# univ_3-2-1-x-rev2.net
KiCad netlist of a schematic drawn in EAGLE
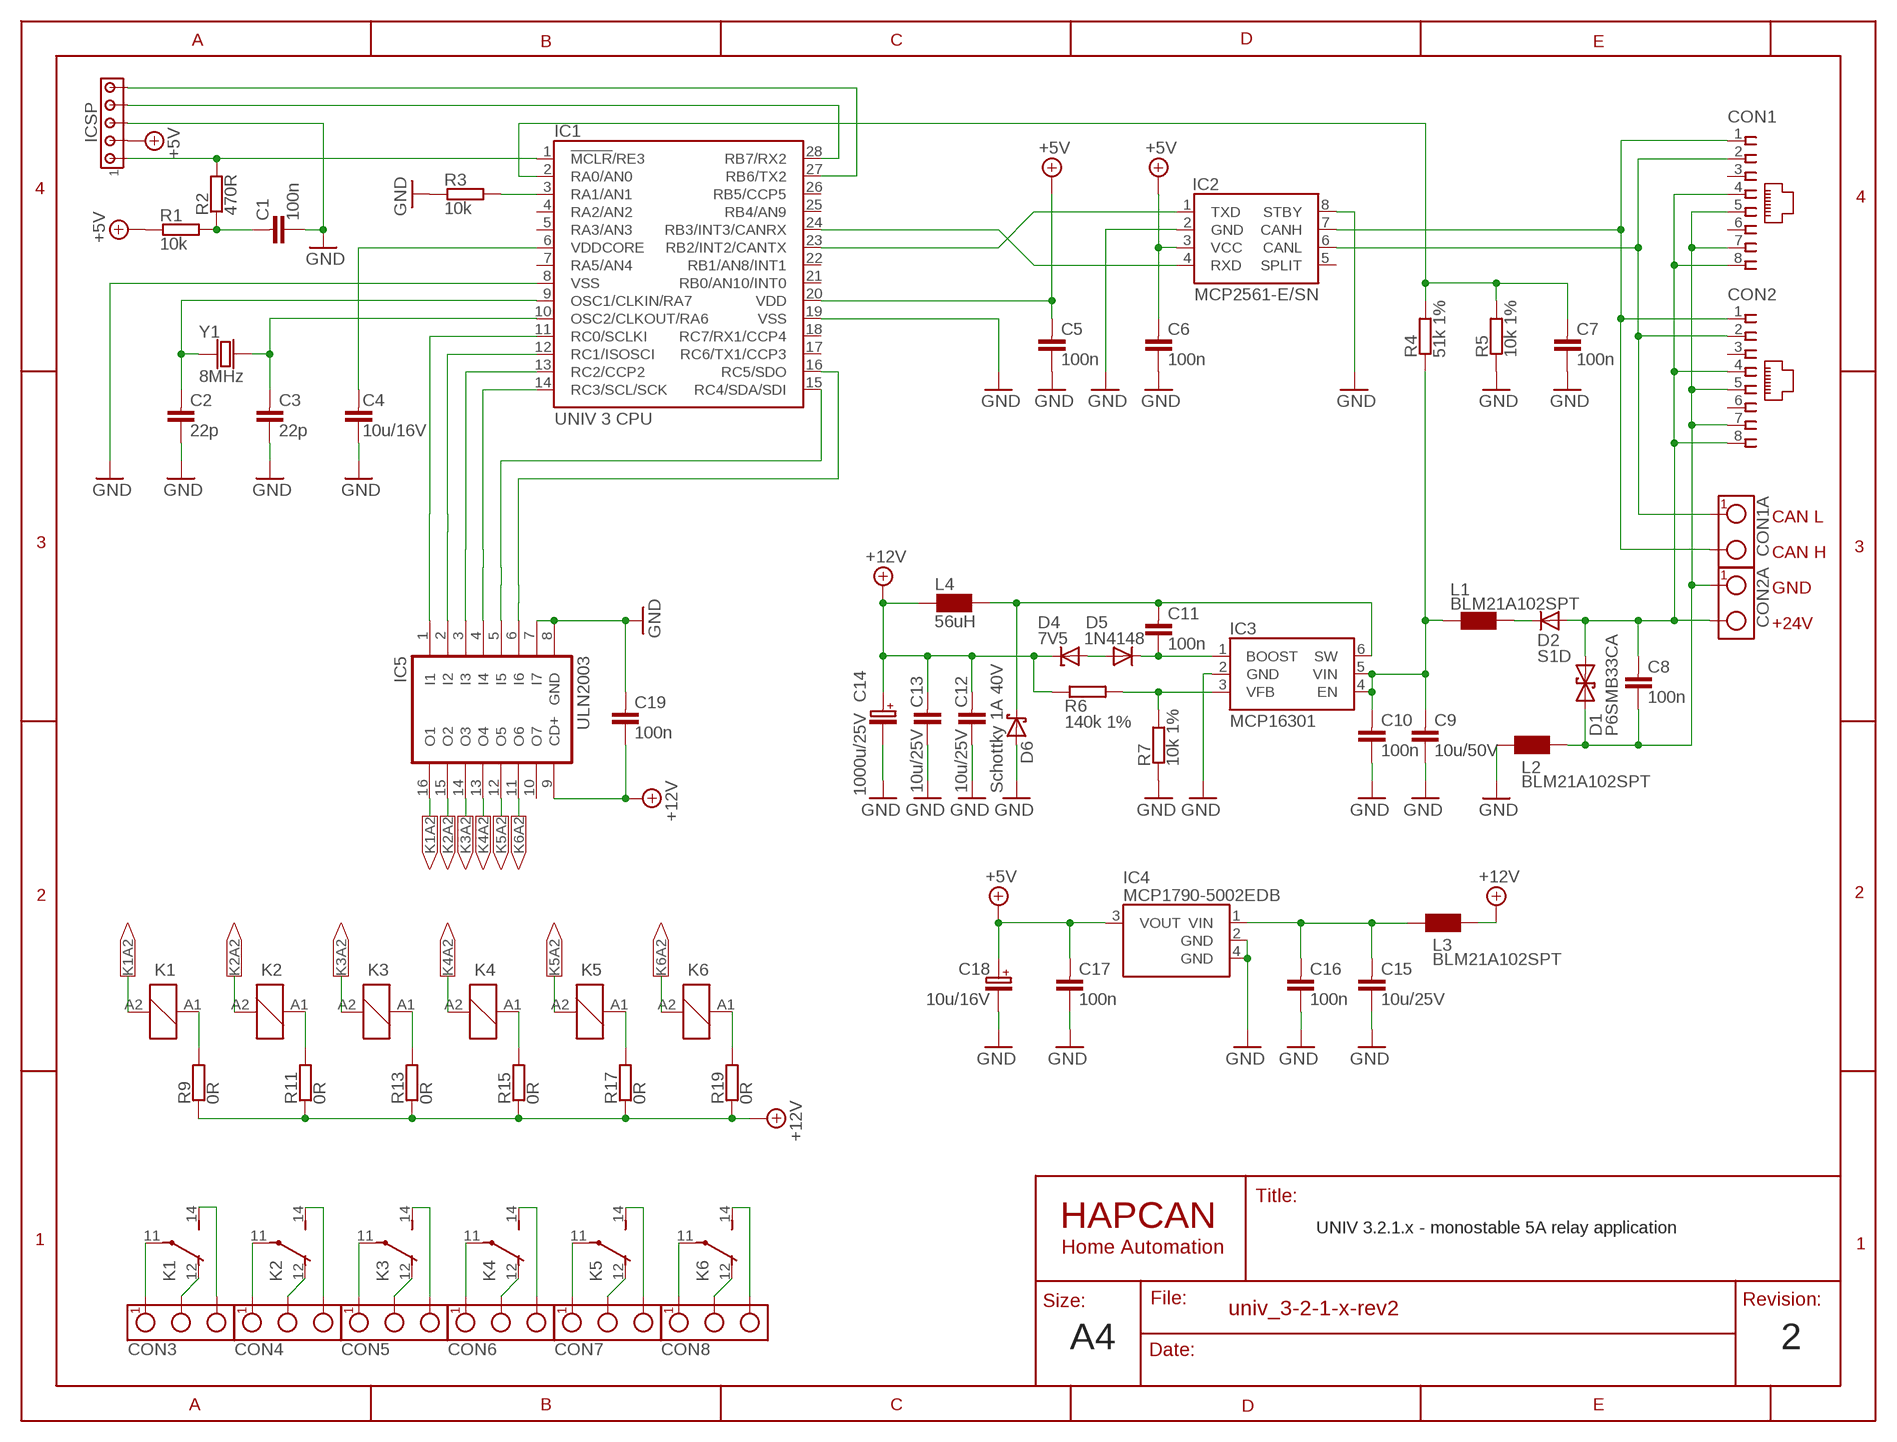
[diagram p0: schematic, sheet 1]

(export (version "E")
  (design (tool "Eeschema 10.0.6"))
  (components
    (comp (ref "C1")
      (value "100n")
      (footprint "eagle-import:0805")
      (libsource (lib "eagle-import") (part "CAPACITOR0805"))
    )
    (comp (ref "C2")
      (value "22p")
      (footprint "eagle-import:0805")
      (libsource (lib "eagle-import") (part "CAPACITOR0805"))
    )
    (comp (ref "C3")
      (value "22p")
      (footprint "eagle-import:0805")
      (libsource (lib "eagle-import") (part "CAPACITOR0805"))
    )
    (comp (ref "C4")
      (value "10u/16V")
      (footprint "eagle-import:0805")
      (libsource (lib "eagle-import") (part "CAPACITOR0805"))
    )
    (comp (ref "C5")
      (value "100n")
      (footprint "eagle-import:0805")
      (libsource (lib "eagle-import") (part "CAPACITOR0805"))
    )
    (comp (ref "C6")
      (value "100n")
      (footprint "eagle-import:0805")
      (libsource (lib "eagle-import") (part "CAPACITOR0805"))
    )
    (comp (ref "C7")
      (value "100n")
      (footprint "eagle-import:0805")
      (libsource (lib "eagle-import") (part "CAPACITOR0805"))
    )
    (comp (ref "C8")
      (value "100n")
      (footprint "eagle-import:0805")
      (libsource (lib "eagle-import") (part "CAPACITOR0805"))
    )
    (comp (ref "C9")
      (value "10u/50V")
      (footprint "eagle-import:1210")
      (libsource (lib "eagle-import") (part "CAPACITOR1210"))
    )
    (comp (ref "C10")
      (value "100n")
      (footprint "eagle-import:0805")
      (libsource (lib "eagle-import") (part "CAPACITOR0805"))
    )
    (comp (ref "C11")
      (value "100n")
      (footprint "eagle-import:0805")
      (libsource (lib "eagle-import") (part "CAPACITOR0805"))
    )
    (comp (ref "C12")
      (value "10u/25V")
      (footprint "eagle-import:1206")
      (libsource (lib "eagle-import") (part "CAPACITOR1206"))
    )
    (comp (ref "C13")
      (value "10u/25V")
      (footprint "eagle-import:1206")
      (libsource (lib "eagle-import") (part "CAPACITOR1206"))
    )
    (comp (ref "C14")
      (value "1000u/25V")
      (footprint "eagle-import:CAP-5X10.5")
      (libsource (lib "eagle-import") (part "CAPACITOR-POLARIZED-5X10.5"))
    )
    (comp (ref "C15")
      (value "10u/25V")
      (footprint "eagle-import:1206")
      (libsource (lib "eagle-import") (part "CAPACITOR1206"))
    )
    (comp (ref "C16")
      (value "100n")
      (footprint "eagle-import:0805")
      (libsource (lib "eagle-import") (part "CAPACITOR0805"))
    )
    (comp (ref "C17")
      (value "100n")
      (footprint "eagle-import:0805")
      (libsource (lib "eagle-import") (part "CAPACITOR0805"))
    )
    (comp (ref "C18")
      (value "10u/16V")
      (footprint "eagle-import:SMC_B")
      (libsource (lib "eagle-import") (part "CAPACITOR-POLARIZED-SMC_B"))
    )
    (comp (ref "C19")
      (value "100n")
      (footprint "eagle-import:0805")
      (libsource (lib "eagle-import") (part "CAPACITOR0805"))
    )
    (comp (ref "CON1")
      (value "RJ45-SOCKET")
      (footprint "eagle-import:RJ45-PCB-SOCKET")
      (libsource (lib "eagle-import") (part "RJ45-SOCKET"))
    )
    (comp (ref "CON1A")
      (value "TERMINAL-2")
      (footprint "eagle-import:ARK2-5X10,5MM")
      (libsource (lib "eagle-import") (part "TERMINAL-2-5X10,5MM"))
    )
    (comp (ref "CON2")
      (value "RJ45-SOCKET")
      (footprint "eagle-import:RJ45-PCB-SOCKET")
      (libsource (lib "eagle-import") (part "RJ45-SOCKET"))
    )
    (comp (ref "CON2A")
      (value "TERMINAL-2")
      (footprint "eagle-import:ARK2-5X10,5MM")
      (libsource (lib "eagle-import") (part "TERMINAL-2-5X10,5MM"))
    )
    (comp (ref "CON3")
      (value "TERMINAL-3-5X10.5MM")
      (footprint "eagle-import:ARK3-5X10.5MM")
      (libsource (lib "eagle-import") (part "TERMINAL-3-5X10.5MM"))
    )
    (comp (ref "CON4")
      (value "TERMINAL-3-5X10.5MM")
      (footprint "eagle-import:ARK3-5X10.5MM")
      (libsource (lib "eagle-import") (part "TERMINAL-3-5X10.5MM"))
    )
    (comp (ref "CON5")
      (value "TERMINAL-3-5X10.5MM")
      (footprint "eagle-import:ARK3-5X10.5MM")
      (libsource (lib "eagle-import") (part "TERMINAL-3-5X10.5MM"))
    )
    (comp (ref "CON6")
      (value "TERMINAL-3-5X10.5MM")
      (footprint "eagle-import:ARK3-5X10.5MM")
      (libsource (lib "eagle-import") (part "TERMINAL-3-5X10.5MM"))
    )
    (comp (ref "CON7")
      (value "TERMINAL-3-5X10.5MM")
      (footprint "eagle-import:ARK3-5X10.5MM")
      (libsource (lib "eagle-import") (part "TERMINAL-3-5X10.5MM"))
    )
    (comp (ref "CON8")
      (value "TERMINAL-3-5X10.5MM")
      (footprint "eagle-import:ARK3-5X10.5MM")
      (libsource (lib "eagle-import") (part "TERMINAL-3-5X10.5MM"))
    )
    (comp (ref "D1")
      (value "P6SMB33CA")
      (footprint "eagle-import:DO-214_TRANSIL2")
      (libsource (lib "eagle-import") (part "DIODE_TRANSIL2"))
    )
    (comp (ref "D2")
      (value "S1D")
      (footprint "eagle-import:DO-214")
      (libsource (lib "eagle-import") (part "DIODE_DO-214"))
    )
    (comp (ref "D4")
      (value "7V5")
      (footprint "eagle-import:SOD-80")
      (libsource (lib "eagle-import") (part "DIODE_ZENER_SOD-80"))
    )
    (comp (ref "D5")
      (value "1N4148")
      (footprint "eagle-import:0805")
      (libsource (lib "eagle-import") (part "DIODE_0805"))
    )
    (comp (ref "D6")
      (value "Schottky 1A 40V")
      (footprint "eagle-import:DO-214")
      (libsource (lib "eagle-import") (part "DIODE_TRANSIL1_DO214"))
    )
    (comp (ref "IC1")
      (value "UNIV 3 CPU")
      (footprint "eagle-import:UNIV3CPU")
      (libsource (lib "eagle-import") (part "UNIV3CPU-I/SO"))
    )
    (comp (ref "IC2")
      (value "MCP2561-E/SN")
      (footprint "eagle-import:SO-08")
      (libsource (lib "eagle-import") (part "MCP2561-E/SN"))
    )
    (comp (ref "IC3")
      (value "MCP16301")
      (footprint "eagle-import:SOT-23-6")
      (libsource (lib "eagle-import") (part "MCP16301SOT23-6"))
    )
    (comp (ref "IC4")
      (value "MCP1790-5002EDB")
      (footprint "eagle-import:SOT-223")
      (libsource (lib "eagle-import") (part "MCP1826SOT223-3"))
    )
    (comp (ref "IC5")
      (value "ULN2003")
      (footprint "eagle-import:SO-16")
      (libsource (lib "eagle-import") (part "ULN2003"))
    )
    (comp (ref "ICSP")
      (value "HEADER5")
      (footprint "eagle-import:SIP-5")
      (libsource (lib "eagle-import") (part "HEADER5"))
    )
    (comp (ref "K1")
      (value "RELAY_PE")
      (footprint "eagle-import:RELAY_PE")
      (libsource (lib "eagle-import") (part "RELAY_PE"))
    )
    (comp (ref "K2")
      (value "RELAY_PE")
      (footprint "eagle-import:RELAY_PE")
      (libsource (lib "eagle-import") (part "RELAY_PE"))
    )
    (comp (ref "K3")
      (value "RELAY_PE")
      (footprint "eagle-import:RELAY_PE")
      (libsource (lib "eagle-import") (part "RELAY_PE"))
    )
    (comp (ref "K4")
      (value "RELAY_PE")
      (footprint "eagle-import:RELAY_PE")
      (libsource (lib "eagle-import") (part "RELAY_PE"))
    )
    (comp (ref "K5")
      (value "RELAY_PE")
      (footprint "eagle-import:RELAY_PE")
      (libsource (lib "eagle-import") (part "RELAY_PE"))
    )
    (comp (ref "K6")
      (value "RELAY_PE")
      (footprint "eagle-import:RELAY_PE")
      (libsource (lib "eagle-import") (part "RELAY_PE"))
    )
    (comp (ref "L1")
      (value "BLM21A102SPT")
      (footprint "eagle-import:0805")
      (libsource (lib "eagle-import") (part "CHOKE0805"))
    )
    (comp (ref "L2")
      (value "BLM21A102SPT")
      (footprint "eagle-import:0805")
      (libsource (lib "eagle-import") (part "CHOKE0805"))
    )
    (comp (ref "L3")
      (value "BLM21A102SPT")
      (footprint "eagle-import:0805")
      (libsource (lib "eagle-import") (part "CHOKE0805"))
    )
    (comp (ref "L4")
      (value "56uH")
      (footprint "eagle-import:CHOKE-DER0705")
      (libsource (lib "eagle-import") (part "CHOKEDER0705"))
    )
    (comp (ref "R1")
      (value "10k")
      (footprint "eagle-import:0805")
      (libsource (lib "eagle-import") (part "RESISTOR0805"))
    )
    (comp (ref "R2")
      (value "470R")
      (footprint "eagle-import:0805")
      (libsource (lib "eagle-import") (part "RESISTOR0805"))
    )
    (comp (ref "R3")
      (value "10k")
      (footprint "eagle-import:0805")
      (libsource (lib "eagle-import") (part "RESISTOR0805"))
    )
    (comp (ref "R4")
      (value "51k 1%")
      (footprint "eagle-import:0805")
      (libsource (lib "eagle-import") (part "RESISTOR0805"))
    )
    (comp (ref "R5")
      (value "10k 1%")
      (footprint "eagle-import:0805")
      (libsource (lib "eagle-import") (part "RESISTOR0805"))
    )
    (comp (ref "R6")
      (value "140k 1%")
      (footprint "eagle-import:0805")
      (libsource (lib "eagle-import") (part "RESISTOR0805"))
    )
    (comp (ref "R7")
      (value "10k 1%")
      (footprint "eagle-import:0805")
      (libsource (lib "eagle-import") (part "RESISTOR0805"))
    )
    (comp (ref "R9")
      (value "0R")
      (footprint "eagle-import:1206")
      (libsource (lib "eagle-import") (part "RESISTOR1206"))
    )
    (comp (ref "R11")
      (value "0R")
      (footprint "eagle-import:1206")
      (libsource (lib "eagle-import") (part "RESISTOR1206"))
    )
    (comp (ref "R13")
      (value "0R")
      (footprint "eagle-import:1206")
      (libsource (lib "eagle-import") (part "RESISTOR1206"))
    )
    (comp (ref "R15")
      (value "0R")
      (footprint "eagle-import:1206")
      (libsource (lib "eagle-import") (part "RESISTOR1206"))
    )
    (comp (ref "R17")
      (value "0R")
      (footprint "eagle-import:1206")
      (libsource (lib "eagle-import") (part "RESISTOR1206"))
    )
    (comp (ref "R19")
      (value "0R")
      (footprint "eagle-import:1206")
      (libsource (lib "eagle-import") (part "RESISTOR1206"))
    )
    (comp (ref "Y1")
      (value "8MHz")
      (footprint "eagle-import:CRYSTAL-HC49V")
      (libsource (lib "eagle-import") (part "CRYSTAL-HC49V"))
    )
  )
  (nets
    (net (code "1") (name "+5V") (class "Default")
      (node (ref "C17") (pin "1") (pinfunction "1_1") (pintype "passive"))
      (node (ref "C18") (pin "+") (pinfunction "1_+") (pintype "passive"))
      (node (ref "C5") (pin "1") (pinfunction "1_1") (pintype "passive"))
      (node (ref "C6") (pin "1") (pinfunction "1_1") (pintype "passive"))
      (node (ref "IC1") (pin "20") (pinfunction "VDD_20") (pintype "bidirectional"))
      (node (ref "IC2") (pin "3") (pinfunction "VCC_3") (pintype "bidirectional"))
      (node (ref "IC4") (pin "3") (pinfunction "VOUT_3") (pintype "bidirectional"))
      (node (ref "ICSP") (pin "2") (pinfunction "2_2") (pintype "passive"))
      (node (ref "R1") (pin "1") (pinfunction "1_1") (pintype "passive"))
    )
    (net (code "2") (name "+12V") (class "Default")
      (node (ref "C12") (pin "1") (pinfunction "1_1") (pintype "passive"))
      (node (ref "C13") (pin "1") (pinfunction "1_1") (pintype "passive"))
      (node (ref "C14") (pin "+") (pinfunction "1_+") (pintype "passive"))
      (node (ref "C19") (pin "2") (pinfunction "2_2") (pintype "passive"))
      (node (ref "D4") (pin "C") (pinfunction "C_C") (pintype "passive"))
      (node (ref "IC5") (pin "9") (pinfunction "CD+_9") (pintype "passive"))
      (node (ref "L3") (pin "2") (pinfunction "2_2") (pintype "passive"))
      (node (ref "L4") (pin "1") (pinfunction "1_1") (pintype "passive"))
      (node (ref "R11") (pin "1") (pinfunction "1_1") (pintype "passive"))
      (node (ref "R13") (pin "1") (pinfunction "1_1") (pintype "passive"))
      (node (ref "R15") (pin "1") (pinfunction "1_1") (pintype "passive"))
      (node (ref "R17") (pin "1") (pinfunction "1_1") (pintype "passive"))
      (node (ref "R19") (pin "1") (pinfunction "1_1") (pintype "passive"))
      (node (ref "R6") (pin "1") (pinfunction "1_1") (pintype "passive"))
      (node (ref "R9") (pin "1") (pinfunction "1_1") (pintype "passive"))
    )
    (net (code "3") (name "/K1A2") (class "Default")
      (node (ref "IC5") (pin "16") (pinfunction "O1_16") (pintype "open_collector"))
      (node (ref "K1") (pin "A2") (pinfunction "2_A2") (pintype "passive"))
    )
    (net (code "4") (name "/K2A2") (class "Default")
      (node (ref "IC5") (pin "15") (pinfunction "O2_15") (pintype "open_collector"))
      (node (ref "K2") (pin "A2") (pinfunction "2_A2") (pintype "passive"))
    )
    (net (code "5") (name "/K3A2") (class "Default")
      (node (ref "IC5") (pin "14") (pinfunction "O3_14") (pintype "open_collector"))
      (node (ref "K3") (pin "A2") (pinfunction "2_A2") (pintype "passive"))
    )
    (net (code "6") (name "/K4A2") (class "Default")
      (node (ref "IC5") (pin "13") (pinfunction "O4_13") (pintype "open_collector"))
      (node (ref "K4") (pin "A2") (pinfunction "2_A2") (pintype "passive"))
    )
    (net (code "7") (name "/K5A2") (class "Default")
      (node (ref "IC5") (pin "12") (pinfunction "O5_12") (pintype "open_collector"))
      (node (ref "K5") (pin "A2") (pinfunction "2_A2") (pintype "passive"))
    )
    (net (code "8") (name "/K6A2") (class "Default")
      (node (ref "IC5") (pin "11") (pinfunction "O6_11") (pintype "open_collector"))
      (node (ref "K6") (pin "A2") (pinfunction "2_A2") (pintype "passive"))
    )
    (net (code "9") (name "GND") (class "Default")
      (node (ref "C1") (pin "2") (pinfunction "2_2") (pintype "passive"))
      (node (ref "C10") (pin "2") (pinfunction "2_2") (pintype "passive"))
      (node (ref "C12") (pin "2") (pinfunction "2_2") (pintype "passive"))
      (node (ref "C13") (pin "2") (pinfunction "2_2") (pintype "passive"))
      (node (ref "C14") (pin "-") (pinfunction "2_-") (pintype "passive"))
      (node (ref "C15") (pin "2") (pinfunction "2_2") (pintype "passive"))
      (node (ref "C16") (pin "2") (pinfunction "2_2") (pintype "passive"))
      (node (ref "C17") (pin "2") (pinfunction "2_2") (pintype "passive"))
      (node (ref "C18") (pin "-") (pinfunction "2_-") (pintype "passive"))
      (node (ref "C19") (pin "1") (pinfunction "1_1") (pintype "passive"))
      (node (ref "C2") (pin "2") (pinfunction "2_2") (pintype "passive"))
      (node (ref "C3") (pin "2") (pinfunction "2_2") (pintype "passive"))
      (node (ref "C4") (pin "2") (pinfunction "2_2") (pintype "passive"))
      (node (ref "C5") (pin "2") (pinfunction "2_2") (pintype "passive"))
      (node (ref "C6") (pin "2") (pinfunction "2_2") (pintype "passive"))
      (node (ref "C7") (pin "2") (pinfunction "2_2") (pintype "passive"))
      (node (ref "C9") (pin "2") (pinfunction "2_2") (pintype "passive"))
      (node (ref "D6") (pin "A") (pinfunction "A_A") (pintype "passive"))
      (node (ref "IC1") (pin "19") (pinfunction "VSS_19") (pintype "bidirectional"))
      (node (ref "IC1") (pin "8") (pinfunction "VSS_8") (pintype "bidirectional"))
      (node (ref "IC2") (pin "2") (pinfunction "GND_2") (pintype "bidirectional"))
      (node (ref "IC2") (pin "8") (pinfunction "STBY_8") (pintype "bidirectional"))
      (node (ref "IC3") (pin "2") (pinfunction "GND_2") (pintype "bidirectional"))
      (node (ref "IC4") (pin "2") (pinfunction "GND_2") (pintype "bidirectional"))
      (node (ref "IC4") (pin "4") (pinfunction "GND_4") (pintype "bidirectional"))
      (node (ref "IC5") (pin "7") (pinfunction "I7_7") (pintype "input"))
      (node (ref "IC5") (pin "8") (pinfunction "GND_8") (pintype "power_in"))
      (node (ref "ICSP") (pin "3") (pinfunction "3_3") (pintype "passive"))
      (node (ref "L2") (pin "1") (pinfunction "1_1") (pintype "passive"))
      (node (ref "R3") (pin "1") (pinfunction "1_1") (pintype "passive"))
      (node (ref "R5") (pin "1") (pinfunction "1_1") (pintype "passive"))
      (node (ref "R7") (pin "1") (pinfunction "1_1") (pintype "passive"))
    )
    (net (code "10") (name "Net-(C1-Pad1)") (class "Default")
      (node (ref "C1") (pin "1") (pinfunction "1_1") (pintype "passive"))
      (node (ref "R1") (pin "2") (pinfunction "2_2") (pintype "passive"))
      (node (ref "R2") (pin "1") (pinfunction "1_1") (pintype "passive"))
    )
    (net (code "11") (name "Net-(D1-1)") (class "Default")
      (node (ref "C8") (pin "2") (pinfunction "2_2") (pintype "passive"))
      (node (ref "CON1") (pin "5") (pinfunction "5_5") (pintype "passive"))
      (node (ref "CON1") (pin "7") (pinfunction "7_7") (pintype "passive"))
      (node (ref "CON2") (pin "5") (pinfunction "5_5") (pintype "passive"))
      (node (ref "CON2") (pin "7") (pinfunction "7_7") (pintype "passive"))
      (node (ref "CON2A") (pin "1") (pinfunction "1_1") (pintype "passive"))
      (node (ref "D1") (pin "A") (pinfunction "1_A") (pintype "passive"))
      (node (ref "L2") (pin "2") (pinfunction "2_2") (pintype "passive"))
    )
    (net (code "12") (name "Net-(D1-2)") (class "Default")
      (node (ref "C8") (pin "1") (pinfunction "1_1") (pintype "passive"))
      (node (ref "CON1") (pin "4") (pinfunction "4_4") (pintype "passive"))
      (node (ref "CON1") (pin "8") (pinfunction "8_8") (pintype "passive"))
      (node (ref "CON2") (pin "4") (pinfunction "4_4") (pintype "passive"))
      (node (ref "CON2") (pin "8") (pinfunction "8_8") (pintype "passive"))
      (node (ref "CON2A") (pin "2") (pinfunction "2_2") (pintype "passive"))
      (node (ref "D1") (pin "C") (pinfunction "2_C") (pintype "passive"))
      (node (ref "D2") (pin "A") (pinfunction "A_A") (pintype "passive"))
    )
    (net (code "13") (name "Net-(D2-PadC)") (class "Default")
      (node (ref "D2") (pin "C") (pinfunction "C_C") (pintype "passive"))
      (node (ref "L1") (pin "2") (pinfunction "2_2") (pintype "passive"))
    )
    (net (code "14") (name "Net-(D5-A)") (class "Default")
      (node (ref "D4") (pin "A") (pinfunction "A_A") (pintype "passive"))
      (node (ref "D5") (pin "2") (pinfunction "A_2") (pintype "passive"))
    )
    (net (code "15") (name "Net-(D5-C)") (class "Default")
      (node (ref "C11") (pin "2") (pinfunction "2_2") (pintype "passive"))
      (node (ref "D5") (pin "1") (pinfunction "C_1") (pintype "passive"))
      (node (ref "IC3") (pin "1") (pinfunction "BOOST_1") (pintype "bidirectional"))
    )
    (net (code "16") (name "Net-(IC1-OSC1{slash}CLKIN{slash}RA7)") (class "Default")
      (node (ref "C2") (pin "1") (pinfunction "1_1") (pintype "passive"))
      (node (ref "IC1") (pin "9") (pinfunction "OSC1/CLKIN/RA7_9") (pintype "bidirectional"))
      (node (ref "Y1") (pin "1") (pinfunction "1_1") (pintype "passive"))
    )
    (net (code "17") (name "Net-(IC1-OSC2{slash}CLKOUT{slash}RA6)") (class "Default")
      (node (ref "C3") (pin "1") (pinfunction "1_1") (pintype "passive"))
      (node (ref "IC1") (pin "10") (pinfunction "OSC2/CLKOUT/RA6_10") (pintype "bidirectional"))
      (node (ref "Y1") (pin "2") (pinfunction "2_2") (pintype "passive"))
    )
    (net (code "18") (name "Net-(IC1-RA0{slash}AN0)") (class "Default")
      (node (ref "C7") (pin "1") (pinfunction "1_1") (pintype "passive"))
      (node (ref "IC1") (pin "2") (pinfunction "RA0/AN0_2") (pintype "bidirectional"))
      (node (ref "R4") (pin "2") (pinfunction "2_2") (pintype "passive"))
      (node (ref "R5") (pin "2") (pinfunction "2_2") (pintype "passive"))
    )
    (net (code "19") (name "Net-(IC1-RA1{slash}AN1)") (class "Default")
      (node (ref "IC1") (pin "3") (pinfunction "RA1/AN1_3") (pintype "bidirectional"))
      (node (ref "R3") (pin "2") (pinfunction "2_2") (pintype "passive"))
    )
    (net (code "20") (name "Net-(IC1-RB2{slash}INT2{slash}CANTX)") (class "Default")
      (node (ref "IC1") (pin "23") (pinfunction "RB2/INT2/CANTX_23") (pintype "bidirectional"))
      (node (ref "IC2") (pin "1") (pinfunction "TXD_1") (pintype "bidirectional"))
    )
    (net (code "21") (name "Net-(IC1-RB3{slash}INT3{slash}CANRX)") (class "Default")
      (node (ref "IC1") (pin "24") (pinfunction "RB3/INT3/CANRX_24") (pintype "bidirectional"))
      (node (ref "IC2") (pin "4") (pinfunction "RXD_4") (pintype "bidirectional"))
    )
    (net (code "22") (name "Net-(IC1-RB6{slash}TX2)") (class "Default")
      (node (ref "IC1") (pin "27") (pinfunction "RB6/TX2_27") (pintype "bidirectional"))
      (node (ref "ICSP") (pin "5") (pinfunction "5_5") (pintype "passive"))
    )
    (net (code "23") (name "Net-(IC1-RB7{slash}RX2)") (class "Default")
      (node (ref "IC1") (pin "28") (pinfunction "RB7/RX2_28") (pintype "bidirectional"))
      (node (ref "ICSP") (pin "4") (pinfunction "4_4") (pintype "passive"))
    )
    (net (code "24") (name "Net-(IC1-RC0{slash}SCLKI)") (class "Default")
      (node (ref "IC1") (pin "11") (pinfunction "RC0/SCLKI_11") (pintype "bidirectional"))
      (node (ref "IC5") (pin "1") (pinfunction "I1_1") (pintype "input"))
    )
    (net (code "25") (name "Net-(IC1-RC1{slash}ISOSCI)") (class "Default")
      (node (ref "IC1") (pin "12") (pinfunction "RC1/ISOSCI_12") (pintype "bidirectional"))
      (node (ref "IC5") (pin "2") (pinfunction "I2_2") (pintype "input"))
    )
    (net (code "26") (name "Net-(IC1-RC2{slash}CCP2)") (class "Default")
      (node (ref "IC1") (pin "13") (pinfunction "RC2/CCP2_13") (pintype "bidirectional"))
      (node (ref "IC5") (pin "3") (pinfunction "I3_3") (pintype "input"))
    )
    (net (code "27") (name "Net-(IC1-RC3{slash}SCL{slash}SCK)") (class "Default")
      (node (ref "IC1") (pin "14") (pinfunction "RC3/SCL/SCK_14") (pintype "bidirectional"))
      (node (ref "IC5") (pin "4") (pinfunction "I4_4") (pintype "input"))
    )
    (net (code "28") (name "Net-(IC1-RC4{slash}SDA{slash}SDI)") (class "Default")
      (node (ref "IC1") (pin "15") (pinfunction "RC4/SDA/SDI_15") (pintype "bidirectional"))
      (node (ref "IC5") (pin "5") (pinfunction "I5_5") (pintype "input"))
    )
    (net (code "29") (name "Net-(IC1-RC5{slash}SDO)") (class "Default")
      (node (ref "IC1") (pin "16") (pinfunction "RC5/SDO_16") (pintype "bidirectional"))
      (node (ref "IC5") (pin "6") (pinfunction "I6_6") (pintype "input"))
    )
    (net (code "30") (name "Net-(IC1-VDDCORE)") (class "Default")
      (node (ref "C4") (pin "1") (pinfunction "1_1") (pintype "passive"))
      (node (ref "IC1") (pin "6") (pinfunction "VDDCORE_6") (pintype "bidirectional"))
    )
    (net (code "31") (name "Net-(IC1-~{MCLR}{slash}RE3)") (class "Default")
      (node (ref "IC1") (pin "1") (pinfunction "~{MCLR}/RE3_1") (pintype "bidirectional"))
      (node (ref "ICSP") (pin "1") (pinfunction "1_1") (pintype "passive"))
      (node (ref "R2") (pin "2") (pinfunction "2_2") (pintype "passive"))
    )
    (net (code "32") (name "Net-(IC2-CANH)") (class "Default")
      (node (ref "CON1") (pin "1") (pinfunction "1_1") (pintype "passive"))
      (node (ref "CON1A") (pin "2") (pinfunction "2_2") (pintype "passive"))
      (node (ref "CON2") (pin "1") (pinfunction "1_1") (pintype "passive"))
      (node (ref "IC2") (pin "7") (pinfunction "CANH_7") (pintype "bidirectional"))
    )
    (net (code "33") (name "Net-(IC2-CANL)") (class "Default")
      (node (ref "CON1") (pin "2") (pinfunction "2_2") (pintype "passive"))
      (node (ref "CON1A") (pin "1") (pinfunction "1_1") (pintype "passive"))
      (node (ref "CON2") (pin "2") (pinfunction "2_2") (pintype "passive"))
      (node (ref "IC2") (pin "6") (pinfunction "CANL_6") (pintype "bidirectional"))
    )
    (net (code "34") (name "Net-(IC3-EN)") (class "Default")
      (node (ref "C10") (pin "1") (pinfunction "1_1") (pintype "passive"))
      (node (ref "C9") (pin "1") (pinfunction "1_1") (pintype "passive"))
      (node (ref "IC3") (pin "4") (pinfunction "EN_4") (pintype "bidirectional"))
      (node (ref "IC3") (pin "5") (pinfunction "VIN_5") (pintype "bidirectional"))
      (node (ref "L1") (pin "1") (pinfunction "1_1") (pintype "passive"))
      (node (ref "R4") (pin "1") (pinfunction "1_1") (pintype "passive"))
    )
    (net (code "35") (name "Net-(IC3-SW)") (class "Default")
      (node (ref "C11") (pin "1") (pinfunction "1_1") (pintype "passive"))
      (node (ref "D6") (pin "C") (pinfunction "C_C") (pintype "passive"))
      (node (ref "IC3") (pin "6") (pinfunction "SW_6") (pintype "bidirectional"))
      (node (ref "L4") (pin "2") (pinfunction "2_2") (pintype "passive"))
    )
    (net (code "36") (name "Net-(IC3-VFB)") (class "Default")
      (node (ref "IC3") (pin "3") (pinfunction "VFB_3") (pintype "bidirectional"))
      (node (ref "R6") (pin "2") (pinfunction "2_2") (pintype "passive"))
      (node (ref "R7") (pin "2") (pinfunction "2_2") (pintype "passive"))
    )
    (net (code "37") (name "Net-(IC4-VIN)") (class "Default")
      (node (ref "C15") (pin "1") (pinfunction "1_1") (pintype "passive"))
      (node (ref "C16") (pin "1") (pinfunction "1_1") (pintype "passive"))
      (node (ref "IC4") (pin "1") (pinfunction "VIN_1") (pintype "bidirectional"))
      (node (ref "L3") (pin "1") (pinfunction "1_1") (pintype "passive"))
    )
    (net (code "38") (name "Net-(K1A-1)") (class "Default")
      (node (ref "K1") (pin "A1") (pinfunction "1_A1") (pintype "passive"))
      (node (ref "R9") (pin "2") (pinfunction "2_2") (pintype "passive"))
    )
    (net (code "39") (name "Net-(K1B-COM)") (class "Default")
      (node (ref "CON3") (pin "1") (pinfunction "1_1") (pintype "passive"))
      (node (ref "K1") (pin "11") (pinfunction "COM_11") (pintype "passive"))
    )
    (net (code "40") (name "Net-(K1B-NC)") (class "Default")
      (node (ref "CON3") (pin "2") (pinfunction "2_2") (pintype "passive"))
      (node (ref "K1") (pin "12") (pinfunction "NC_12") (pintype "passive"))
    )
    (net (code "41") (name "Net-(K1B-NO)") (class "Default")
      (node (ref "CON3") (pin "3") (pinfunction "3_3") (pintype "passive"))
      (node (ref "K1") (pin "14") (pinfunction "NO_14") (pintype "passive"))
    )
    (net (code "42") (name "Net-(K2A-1)") (class "Default")
      (node (ref "K2") (pin "A1") (pinfunction "1_A1") (pintype "passive"))
      (node (ref "R11") (pin "2") (pinfunction "2_2") (pintype "passive"))
    )
    (net (code "43") (name "Net-(K2B-COM)") (class "Default")
      (node (ref "CON4") (pin "1") (pinfunction "1_1") (pintype "passive"))
      (node (ref "K2") (pin "11") (pinfunction "COM_11") (pintype "passive"))
    )
    (net (code "44") (name "Net-(K2B-NC)") (class "Default")
      (node (ref "CON4") (pin "2") (pinfunction "2_2") (pintype "passive"))
      (node (ref "K2") (pin "12") (pinfunction "NC_12") (pintype "passive"))
    )
    (net (code "45") (name "Net-(K2B-NO)") (class "Default")
      (node (ref "CON4") (pin "3") (pinfunction "3_3") (pintype "passive"))
      (node (ref "K2") (pin "14") (pinfunction "NO_14") (pintype "passive"))
    )
    (net (code "46") (name "Net-(K3A-1)") (class "Default")
      (node (ref "K3") (pin "A1") (pinfunction "1_A1") (pintype "passive"))
      (node (ref "R13") (pin "2") (pinfunction "2_2") (pintype "passive"))
    )
    (net (code "47") (name "Net-(K3B-COM)") (class "Default")
      (node (ref "CON5") (pin "1") (pinfunction "1_1") (pintype "passive"))
      (node (ref "K3") (pin "11") (pinfunction "COM_11") (pintype "passive"))
    )
    (net (code "48") (name "Net-(K3B-NC)") (class "Default")
      (node (ref "CON5") (pin "2") (pinfunction "2_2") (pintype "passive"))
      (node (ref "K3") (pin "12") (pinfunction "NC_12") (pintype "passive"))
    )
    (net (code "49") (name "Net-(K3B-NO)") (class "Default")
      (node (ref "CON5") (pin "3") (pinfunction "3_3") (pintype "passive"))
      (node (ref "K3") (pin "14") (pinfunction "NO_14") (pintype "passive"))
    )
    (net (code "50") (name "Net-(K4A-1)") (class "Default")
      (node (ref "K4") (pin "A1") (pinfunction "1_A1") (pintype "passive"))
      (node (ref "R15") (pin "2") (pinfunction "2_2") (pintype "passive"))
    )
    (net (code "51") (name "Net-(K4B-COM)") (class "Default")
      (node (ref "CON6") (pin "1") (pinfunction "1_1") (pintype "passive"))
      (node (ref "K4") (pin "11") (pinfunction "COM_11") (pintype "passive"))
    )
    (net (code "52") (name "Net-(K4B-NC)") (class "Default")
      (node (ref "CON6") (pin "2") (pinfunction "2_2") (pintype "passive"))
      (node (ref "K4") (pin "12") (pinfunction "NC_12") (pintype "passive"))
    )
    (net (code "53") (name "Net-(K4B-NO)") (class "Default")
      (node (ref "CON6") (pin "3") (pinfunction "3_3") (pintype "passive"))
      (node (ref "K4") (pin "14") (pinfunction "NO_14") (pintype "passive"))
    )
    (net (code "54") (name "Net-(K5A-1)") (class "Default")
      (node (ref "K5") (pin "A1") (pinfunction "1_A1") (pintype "passive"))
      (node (ref "R17") (pin "2") (pinfunction "2_2") (pintype "passive"))
    )
    (net (code "55") (name "Net-(K5B-COM)") (class "Default")
      (node (ref "CON7") (pin "1") (pinfunction "1_1") (pintype "passive"))
      (node (ref "K5") (pin "11") (pinfunction "COM_11") (pintype "passive"))
    )
    (net (code "56") (name "Net-(K5B-NC)") (class "Default")
      (node (ref "CON7") (pin "2") (pinfunction "2_2") (pintype "passive"))
      (node (ref "K5") (pin "12") (pinfunction "NC_12") (pintype "passive"))
    )
    (net (code "57") (name "Net-(K5B-NO)") (class "Default")
      (node (ref "CON7") (pin "3") (pinfunction "3_3") (pintype "passive"))
      (node (ref "K5") (pin "14") (pinfunction "NO_14") (pintype "passive"))
    )
    (net (code "58") (name "Net-(K6A-1)") (class "Default")
      (node (ref "K6") (pin "A1") (pinfunction "1_A1") (pintype "passive"))
      (node (ref "R19") (pin "2") (pinfunction "2_2") (pintype "passive"))
    )
    (net (code "59") (name "Net-(K6B-COM)") (class "Default")
      (node (ref "CON8") (pin "1") (pinfunction "1_1") (pintype "passive"))
      (node (ref "K6") (pin "11") (pinfunction "COM_11") (pintype "passive"))
    )
    (net (code "60") (name "Net-(K6B-NC)") (class "Default")
      (node (ref "CON8") (pin "2") (pinfunction "2_2") (pintype "passive"))
      (node (ref "K6") (pin "12") (pinfunction "NC_12") (pintype "passive"))
    )
    (net (code "61") (name "Net-(K6B-NO)") (class "Default")
      (node (ref "CON8") (pin "3") (pinfunction "3_3") (pintype "passive"))
      (node (ref "K6") (pin "14") (pinfunction "NO_14") (pintype "passive"))
    )
    (net (code "62") (name "unconnected-(CON1-Pad3)") (class "Default")
      (node (ref "CON1") (pin "3") (pinfunction "3_3") (pintype "passive"))
    )
    (net (code "63") (name "unconnected-(CON1-Pad6)") (class "Default")
      (node (ref "CON1") (pin "6") (pinfunction "6_6") (pintype "passive"))
    )
    (net (code "64") (name "unconnected-(CON2-Pad3)") (class "Default")
      (node (ref "CON2") (pin "3") (pinfunction "3_3") (pintype "passive"))
    )
    (net (code "65") (name "unconnected-(CON2-Pad6)") (class "Default")
      (node (ref "CON2") (pin "6") (pinfunction "6_6") (pintype "passive"))
    )
    (net (code "66") (name "unconnected-(IC1-RA2{slash}AN2-Pad4)") (class "Default")
      (node (ref "IC1") (pin "4") (pinfunction "RA2/AN2_4") (pintype "bidirectional"))
    )
    (net (code "67") (name "unconnected-(IC1-RA3{slash}AN3-Pad5)") (class "Default")
      (node (ref "IC1") (pin "5") (pinfunction "RA3/AN3_5") (pintype "bidirectional"))
    )
    (net (code "68") (name "unconnected-(IC1-RA5{slash}AN4-Pad7)") (class "Default")
      (node (ref "IC1") (pin "7") (pinfunction "RA5/AN4_7") (pintype "bidirectional"))
    )
    (net (code "69") (name "unconnected-(IC1-RB0{slash}AN10{slash}INT0-Pad21)") (class "Default")
      (node (ref "IC1") (pin "21") (pinfunction "RB0/AN10/INT0_21") (pintype "bidirectional"))
    )
    (net (code "70") (name "unconnected-(IC1-RB1{slash}AN8{slash}INT1-Pad22)") (class "Default")
      (node (ref "IC1") (pin "22") (pinfunction "RB1/AN8/INT1_22") (pintype "bidirectional"))
    )
    (net (code "71") (name "unconnected-(IC1-RB4{slash}AN9-Pad25)") (class "Default")
      (node (ref "IC1") (pin "25") (pinfunction "RB4/AN9_25") (pintype "bidirectional"))
    )
    (net (code "72") (name "unconnected-(IC1-RB5{slash}CCP5-Pad26)") (class "Default")
      (node (ref "IC1") (pin "26") (pinfunction "RB5/CCP5_26") (pintype "bidirectional"))
    )
    (net (code "73") (name "unconnected-(IC1-RC6{slash}TX1{slash}CCP3-Pad17)") (class "Default")
      (node (ref "IC1") (pin "17") (pinfunction "RC6/TX1/CCP3_17") (pintype "bidirectional"))
    )
    (net (code "74") (name "unconnected-(IC1-RC7{slash}RX1{slash}CCP4-Pad18)") (class "Default")
      (node (ref "IC1") (pin "18") (pinfunction "RC7/RX1/CCP4_18") (pintype "bidirectional"))
    )
    (net (code "75") (name "unconnected-(IC2-SPLIT-Pad5)") (class "Default")
      (node (ref "IC2") (pin "5") (pinfunction "SPLIT_5") (pintype "bidirectional"))
    )
    (net (code "76") (name "unconnected-(IC5-O7-Pad10)") (class "Default")
      (node (ref "IC5") (pin "10") (pinfunction "O7_10") (pintype "open_collector"))
    )
  )
)
